# TdsReworkSMD.net
KiCad netlist of a schematic drawn in EAGLE
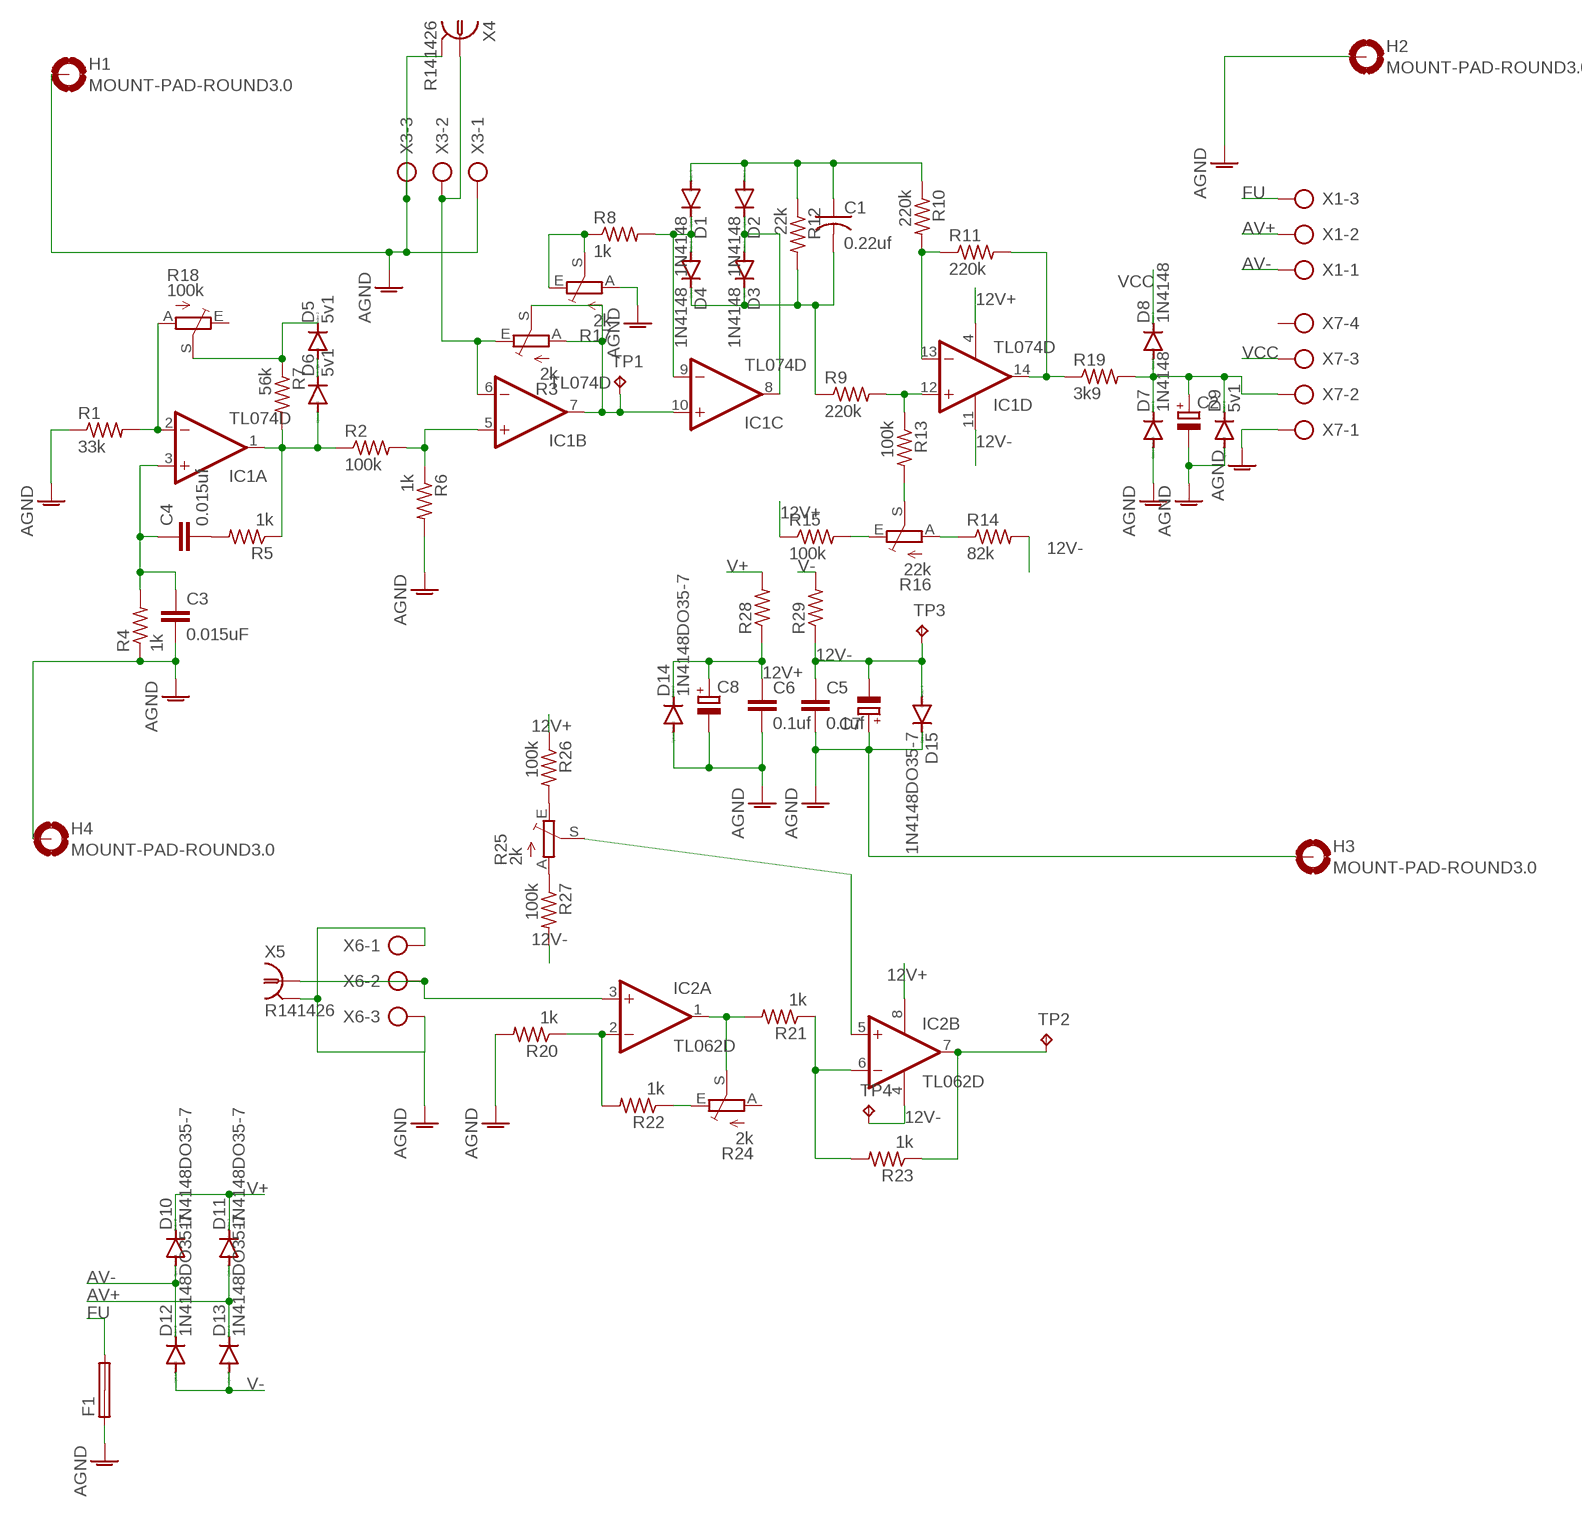
[diagram p0: schematic, sheet 1]

(export (version "E")
  (design (tool "Eeschema 10.0.6"))
  (components
    (comp (ref "C1")
      (value "0.22uf")
      (footprint "eagle-import:C075-032X103")
      (libsource (lib "eagle-import") (part "C-US075-032X103"))
    )
    (comp (ref "C2")
      (value "CPOL-EUE5-8.5")
      (footprint "eagle-import:E5-8,5")
      (libsource (lib "eagle-import") (part "CPOL-EUE5-8.5"))
    )
    (comp (ref "C3")
      (value "0.015uF")
      (footprint "eagle-import:C050-024X044")
      (libsource (lib "eagle-import") (part "C-EU050-024X044"))
    )
    (comp (ref "C4")
      (value "0.015uf")
      (footprint "eagle-import:C050-024X044")
      (libsource (lib "eagle-import") (part "C-EU050-024X044"))
    )
    (comp (ref "C5")
      (value "0.1uf")
      (footprint "eagle-import:C5B2.5")
      (libsource (lib "eagle-import") (part "C5/2.5"))
    )
    (comp (ref "C6")
      (value "0.1uf")
      (footprint "eagle-import:C5B2.5")
      (libsource (lib "eagle-import") (part "C5/2.5"))
    )
    (comp (ref "C7")
      (value "CPOL-EUE5-8.5")
      (footprint "eagle-import:E5-8,5")
      (libsource (lib "eagle-import") (part "CPOL-EUE5-8.5"))
    )
    (comp (ref "C8")
      (value "CPOL-EUE5-8.5")
      (footprint "eagle-import:E5-8,5")
      (libsource (lib "eagle-import") (part "CPOL-EUE5-8.5"))
    )
    (comp (ref "D1")
      (value "1N4148")
      (footprint "eagle-import:DO35-7")
      (libsource (lib "eagle-import") (part "1N4148DO35-7"))
    )
    (comp (ref "D2")
      (value "1N4148")
      (footprint "eagle-import:DO35-7")
      (libsource (lib "eagle-import") (part "1N4148DO35-7"))
    )
    (comp (ref "D3")
      (value "1N4148")
      (footprint "eagle-import:DO35-7")
      (libsource (lib "eagle-import") (part "1N4148DO35-7"))
    )
    (comp (ref "D4")
      (value "1N4148")
      (footprint "eagle-import:DO35-7")
      (libsource (lib "eagle-import") (part "1N4148DO35-7"))
    )
    (comp (ref "D5")
      (value "5v1")
      (footprint "eagle-import:DO35-7")
      (libsource (lib "eagle-import") (part "1N4148DO35-7"))
    )
    (comp (ref "D6")
      (value "5v1")
      (footprint "eagle-import:DO35-7")
      (libsource (lib "eagle-import") (part "1N4148DO35-7"))
    )
    (comp (ref "D7")
      (value "1N4148")
      (footprint "eagle-import:DO35-7")
      (libsource (lib "eagle-import") (part "1N4148DO35-7"))
    )
    (comp (ref "D8")
      (value "1N4148")
      (footprint "eagle-import:DO35-7")
      (libsource (lib "eagle-import") (part "1N4148DO35-7"))
    )
    (comp (ref "D9")
      (value "5v1")
      (footprint "eagle-import:DO35-10")
      (libsource (lib "eagle-import") (part "1N4148DO35-10"))
    )
    (comp (ref "D10")
      (value "1N4148DO35-7")
      (footprint "eagle-import:DO35-7")
      (libsource (lib "eagle-import") (part "1N4148DO35-7"))
    )
    (comp (ref "D11")
      (value "1N4148DO35-7")
      (footprint "eagle-import:DO35-7")
      (libsource (lib "eagle-import") (part "1N4148DO35-7"))
    )
    (comp (ref "D12")
      (value "1N4148DO35-7")
      (footprint "eagle-import:DO35-7")
      (libsource (lib "eagle-import") (part "1N4148DO35-7"))
    )
    (comp (ref "D13")
      (value "1N4148DO35-7")
      (footprint "eagle-import:DO35-7")
      (libsource (lib "eagle-import") (part "1N4148DO35-7"))
    )
    (comp (ref "D14")
      (value "1N4148DO35-7")
      (footprint "eagle-import:DO35-7")
      (libsource (lib "eagle-import") (part "1N4148DO35-7"))
    )
    (comp (ref "D15")
      (value "1N4148DO35-7")
      (footprint "eagle-import:DO35-7")
      (libsource (lib "eagle-import") (part "1N4148DO35-7"))
    )
    (comp (ref "F1")
      (value "SHK20L")
      (footprint "eagle-import:SHK20L")
      (libsource (lib "eagle-import") (part "SHK20L"))
    )
    (comp (ref "H1")
      (value "MOUNT-PAD-ROUND3.0")
      (footprint "eagle-import:3,0-PAD")
      (libsource (lib "eagle-import") (part "MOUNT-PAD-ROUND3.0"))
    )
    (comp (ref "H2")
      (value "MOUNT-PAD-ROUND3.0")
      (footprint "eagle-import:3,0-PAD")
      (libsource (lib "eagle-import") (part "MOUNT-PAD-ROUND3.0"))
    )
    (comp (ref "H3")
      (value "MOUNT-PAD-ROUND3.0")
      (footprint "eagle-import:3,0-PAD")
      (libsource (lib "eagle-import") (part "MOUNT-PAD-ROUND3.0"))
    )
    (comp (ref "H4")
      (value "MOUNT-PAD-ROUND3.0")
      (footprint "eagle-import:3,0-PAD")
      (libsource (lib "eagle-import") (part "MOUNT-PAD-ROUND3.0"))
    )
    (comp (ref "IC1")
      (value "TL074D")
      (footprint "eagle-import:SO14")
      (libsource (lib "eagle-import") (part "TL074D"))
    )
    (comp (ref "IC2")
      (value "TL062D")
      (footprint "eagle-import:SO08")
      (libsource (lib "eagle-import") (part "TL062D"))
    )
    (comp (ref "R1")
      (value "33k")
      (footprint "eagle-import:0204_5")
      (libsource (lib "eagle-import") (part "R-US_0204/5"))
    )
    (comp (ref "R2")
      (value "100k")
      (footprint "eagle-import:0204_5")
      (libsource (lib "eagle-import") (part "R-US_0204/5"))
    )
    (comp (ref "R3")
      (value "2k")
      (footprint "eagle-import:B64Y")
      (libsource (lib "eagle-import") (part "TRIM_EU-B64Y"))
    )
    (comp (ref "R4")
      (value "1k")
      (footprint "eagle-import:0204_5")
      (libsource (lib "eagle-import") (part "R-US_0204/5"))
    )
    (comp (ref "R5")
      (value "1k")
      (footprint "eagle-import:0204_5")
      (libsource (lib "eagle-import") (part "R-US_0204/5"))
    )
    (comp (ref "R6")
      (value "1k")
      (footprint "eagle-import:0204_5")
      (libsource (lib "eagle-import") (part "R-US_0204/5"))
    )
    (comp (ref "R7")
      (value "56k")
      (footprint "eagle-import:0204V")
      (libsource (lib "eagle-import") (part "R-US_0204/2V"))
    )
    (comp (ref "R8")
      (value "1k")
      (footprint "eagle-import:0204_5")
      (libsource (lib "eagle-import") (part "R-US_0204/5"))
    )
    (comp (ref "R9")
      (value "220k")
      (footprint "eagle-import:0204_5")
      (libsource (lib "eagle-import") (part "R-US_0204/5"))
    )
    (comp (ref "R10")
      (value "220k")
      (footprint "eagle-import:0204_5")
      (libsource (lib "eagle-import") (part "R-US_0204/5"))
    )
    (comp (ref "R11")
      (value "220k")
      (footprint "eagle-import:0204_5")
      (libsource (lib "eagle-import") (part "R-US_0204/5"))
    )
    (comp (ref "R12")
      (value "22k")
      (footprint "eagle-import:0204_5")
      (libsource (lib "eagle-import") (part "R-US_0204/5"))
    )
    (comp (ref "R13")
      (value "100k")
      (footprint "eagle-import:0204_5")
      (libsource (lib "eagle-import") (part "R-US_0204/5"))
    )
    (comp (ref "R14")
      (value "82k")
      (footprint "eagle-import:0204_5")
      (libsource (lib "eagle-import") (part "R-US_0204/5"))
    )
    (comp (ref "R15")
      (value "100k")
      (footprint "eagle-import:0204_5")
      (libsource (lib "eagle-import") (part "R-US_0204/5"))
    )
    (comp (ref "R16")
      (value "22k")
      (footprint "eagle-import:B64Y")
      (libsource (lib "eagle-import") (part "TRIM_EU-B64Y"))
    )
    (comp (ref "R17")
      (value "2k")
      (footprint "eagle-import:B64Y")
      (libsource (lib "eagle-import") (part "TRIM_EU-B64Y"))
    )
    (comp (ref "R18")
      (value "100k")
      (footprint "eagle-import:B64Y")
      (libsource (lib "eagle-import") (part "TRIM_EU-B64Y"))
    )
    (comp (ref "R19")
      (value "3k9")
      (footprint "eagle-import:0204_5")
      (libsource (lib "eagle-import") (part "R-US_0204/5"))
    )
    (comp (ref "R20")
      (value "1k")
      (footprint "eagle-import:0204_5")
      (libsource (lib "eagle-import") (part "R-US_0204/5"))
    )
    (comp (ref "R21")
      (value "1k")
      (footprint "eagle-import:0204_5")
      (libsource (lib "eagle-import") (part "R-US_0204/5"))
    )
    (comp (ref "R22")
      (value "1k")
      (footprint "eagle-import:0204_5")
      (libsource (lib "eagle-import") (part "R-US_0204/5"))
    )
    (comp (ref "R23")
      (value "1k")
      (footprint "eagle-import:0204_5")
      (libsource (lib "eagle-import") (part "R-US_0204/5"))
    )
    (comp (ref "R24")
      (value "2k")
      (footprint "eagle-import:B64Y")
      (libsource (lib "eagle-import") (part "TRIM_EU-B64Y"))
    )
    (comp (ref "R25")
      (value "2k")
      (footprint "eagle-import:B64Y")
      (libsource (lib "eagle-import") (part "TRIM_EU-B64Y"))
    )
    (comp (ref "R26")
      (value "100k")
      (footprint "eagle-import:0204_5")
      (libsource (lib "eagle-import") (part "R-US_0204/5"))
    )
    (comp (ref "R27")
      (value "100k")
      (footprint "eagle-import:0204_5")
      (libsource (lib "eagle-import") (part "R-US_0204/5"))
    )
    (comp (ref "R28")
      (value "R-US_0309/10")
      (footprint "eagle-import:0309_10")
      (libsource (lib "eagle-import") (part "R-US_0309/10"))
    )
    (comp (ref "R29")
      (value "R-US_0309/10")
      (footprint "eagle-import:0309_10")
      (libsource (lib "eagle-import") (part "R-US_0309/10"))
    )
    (comp (ref "TP1")
      (value "TPPAD1-13")
      (footprint "eagle-import:P1-13")
      (libsource (lib "eagle-import") (part "TPPAD1-13"))
    )
    (comp (ref "TP2")
      (value "TPPAD1-13")
      (footprint "eagle-import:P1-13")
      (libsource (lib "eagle-import") (part "TPPAD1-13"))
    )
    (comp (ref "TP3")
      (value "TPPAD1-13")
      (footprint "eagle-import:P1-13")
      (libsource (lib "eagle-import") (part "TPPAD1-13"))
    )
    (comp (ref "TP4")
      (value "TPPAD1-13")
      (footprint "eagle-import:P1-13")
      (libsource (lib "eagle-import") (part "TPPAD1-13"))
    )
    (comp (ref "X1")
      (value "AK500/3")
      (footprint "eagle-import:AK500_3")
      (libsource (lib "eagle-import") (part "AK500/3"))
    )
    (comp (ref "X3")
      (value "AK500/3")
      (footprint "eagle-import:AK500_3")
      (libsource (lib "eagle-import") (part "AK500/3"))
    )
    (comp (ref "X4")
      (value "R141426")
      (footprint "eagle-import:R141426")
      (fields (field (name "MF") "FARNELL") (field (name "MPN") "R141426161"))
      (libsource (lib "eagle-import") (part "R141426"))
    )
    (comp (ref "X5")
      (value "R141426")
      (footprint "eagle-import:R141426")
      (fields (field (name "MF") "FARNELL") (field (name "MPN") "R141426161"))
      (libsource (lib "eagle-import") (part "R141426"))
    )
    (comp (ref "X6")
      (value "AK500/3")
      (footprint "eagle-import:AK500_3")
      (libsource (lib "eagle-import") (part "AK500/3"))
    )
    (comp (ref "X7")
      (value "AK500/4")
      (footprint "eagle-import:AK500_4")
      (libsource (lib "eagle-import") (part "AK500/4"))
    )
  )
  (nets
    (net (code "1") (name "/12V+") (class "Default")
      (node (ref "C6") (pin "1") (pinfunction "1_1") (pintype "passive"))
      (node (ref "C8") (pin "+") (pinfunction "+_+") (pintype "passive"))
      (node (ref "D14") (pin "C") (pinfunction "C_C") (pintype "passive"))
      (node (ref "IC1") (pin "4") (pinfunction "V+_4") (pintype "power_in"))
      (node (ref "IC2") (pin "8") (pinfunction "V+_8") (pintype "power_in"))
      (node (ref "R15") (pin "1") (pinfunction "1_1") (pintype "passive"))
      (node (ref "R26") (pin "1") (pinfunction "1_1") (pintype "passive"))
      (node (ref "R28") (pin "1") (pinfunction "1_1") (pintype "passive"))
    )
    (net (code "2") (name "/12V-") (class "Default")
      (node (ref "C5") (pin "1") (pinfunction "1_1") (pintype "passive"))
      (node (ref "C7") (pin "-") (pinfunction "-_-") (pintype "passive"))
      (node (ref "D15") (pin "A") (pinfunction "A_A") (pintype "passive"))
      (node (ref "IC1") (pin "11") (pinfunction "V-_11") (pintype "power_in"))
      (node (ref "IC2") (pin "4") (pinfunction "V-_4") (pintype "power_in"))
      (node (ref "R14") (pin "2") (pinfunction "2_2") (pintype "passive"))
      (node (ref "R27") (pin "2") (pinfunction "2_2") (pintype "passive"))
      (node (ref "R29") (pin "1") (pinfunction "1_1") (pintype "passive"))
      (node (ref "TP3") (pin "TP") (pinfunction "TP_TP") (pintype "input"))
      (node (ref "TP4") (pin "TP") (pinfunction "TP_TP") (pintype "input"))
    )
    (net (code "3") (name "/AV+") (class "Default")
      (node (ref "D11") (pin "A") (pinfunction "A_A") (pintype "passive"))
      (node (ref "D13") (pin "C") (pinfunction "C_C") (pintype "passive"))
      (node (ref "X1") (pin "2") (pinfunction "KL_2") (pintype "passive"))
    )
    (net (code "4") (name "/AV-") (class "Default")
      (node (ref "D10") (pin "A") (pinfunction "A_A") (pintype "passive"))
      (node (ref "D12") (pin "C") (pinfunction "C_C") (pintype "passive"))
      (node (ref "X1") (pin "1") (pinfunction "KL_1") (pintype "passive"))
    )
    (net (code "5") (name "/FU") (class "Default")
      (node (ref "F1") (pin "2A") (pinfunction "2A_2A") (pintype "passive"))
      (node (ref "X1") (pin "3") (pinfunction "KL_3") (pintype "passive"))
    )
    (net (code "6") (name "/V+") (class "Default")
      (node (ref "D10") (pin "C") (pinfunction "C_C") (pintype "passive"))
      (node (ref "D11") (pin "C") (pinfunction "C_C") (pintype "passive"))
      (node (ref "R28") (pin "2") (pinfunction "2_2") (pintype "passive"))
    )
    (net (code "7") (name "/V-") (class "Default")
      (node (ref "D12") (pin "A") (pinfunction "A_A") (pintype "passive"))
      (node (ref "D13") (pin "A") (pinfunction "A_A") (pintype "passive"))
      (node (ref "R29") (pin "2") (pinfunction "2_2") (pintype "passive"))
    )
    (net (code "8") (name "/VCC") (class "Default")
      (node (ref "D8") (pin "C") (pinfunction "C_C") (pintype "passive"))
      (node (ref "X7") (pin "3") (pinfunction "KL_3") (pintype "passive"))
    )
    (net (code "9") (name "AGND") (class "Default")
      (node (ref "C2") (pin "-") (pinfunction "-_-") (pintype "passive"))
      (node (ref "C3") (pin "2") (pinfunction "2_2") (pintype "passive"))
      (node (ref "C5") (pin "2") (pinfunction "2_2") (pintype "passive"))
      (node (ref "C6") (pin "2") (pinfunction "2_2") (pintype "passive"))
      (node (ref "C7") (pin "+") (pinfunction "+_+") (pintype "passive"))
      (node (ref "C8") (pin "-") (pinfunction "-_-") (pintype "passive"))
      (node (ref "D14") (pin "A") (pinfunction "A_A") (pintype "passive"))
      (node (ref "D15") (pin "C") (pinfunction "C_C") (pintype "passive"))
      (node (ref "D7") (pin "A") (pinfunction "A_A") (pintype "passive"))
      (node (ref "D9") (pin "A") (pinfunction "A_A") (pintype "passive"))
      (node (ref "F1") (pin "1A") (pinfunction "1A_1A") (pintype "passive"))
      (node (ref "H1") (pin "B3,0") (pinfunction "MOUNT_B3,0") (pintype "passive"))
      (node (ref "H2") (pin "B3,0") (pinfunction "MOUNT_B3,0") (pintype "passive"))
      (node (ref "H3") (pin "B3,0") (pinfunction "MOUNT_B3,0") (pintype "passive"))
      (node (ref "H4") (pin "B3,0") (pinfunction "MOUNT_B3,0") (pintype "passive"))
      (node (ref "R1") (pin "1") (pinfunction "1_1") (pintype "passive"))
      (node (ref "R17") (pin "A") (pinfunction "A_A") (pintype "passive"))
      (node (ref "R20") (pin "2") (pinfunction "2_2") (pintype "passive"))
      (node (ref "R4") (pin "1") (pinfunction "1_1") (pintype "passive"))
      (node (ref "R6") (pin "2") (pinfunction "2_2") (pintype "passive"))
      (node (ref "X3") (pin "1") (pinfunction "KL_1") (pintype "passive"))
      (node (ref "X3") (pin "3") (pinfunction "KL_3") (pintype "passive"))
      (node (ref "X4") (pin "2") (pinfunction "2_2") (pintype "passive"))
      (node (ref "X4") (pin "3") (pinfunction "2_3") (pintype "passive"))
      (node (ref "X4") (pin "4") (pinfunction "2_4") (pintype "passive"))
      (node (ref "X4") (pin "5") (pinfunction "2_5") (pintype "passive"))
      (node (ref "X5") (pin "2") (pinfunction "2_2") (pintype "passive"))
      (node (ref "X5") (pin "3") (pinfunction "2_3") (pintype "passive"))
      (node (ref "X5") (pin "4") (pinfunction "2_4") (pintype "passive"))
      (node (ref "X5") (pin "5") (pinfunction "2_5") (pintype "passive"))
      (node (ref "X6") (pin "1") (pinfunction "KL_1") (pintype "passive"))
      (node (ref "X6") (pin "3") (pinfunction "KL_3") (pintype "passive"))
      (node (ref "X7") (pin "1") (pinfunction "KL_1") (pintype "passive"))
    )
    (net (code "10") (name "Net-(C1-Pad1)") (class "Default")
      (node (ref "C1") (pin "1") (pinfunction "1_1") (pintype "passive"))
      (node (ref "D1") (pin "A") (pinfunction "A_A") (pintype "passive"))
      (node (ref "D2") (pin "A") (pinfunction "A_A") (pintype "passive"))
      (node (ref "R10") (pin "1") (pinfunction "1_1") (pintype "passive"))
      (node (ref "R12") (pin "1") (pinfunction "1_1") (pintype "passive"))
    )
    (net (code "11") (name "Net-(C1-Pad2)") (class "Default")
      (node (ref "C1") (pin "2") (pinfunction "2_2") (pintype "passive"))
      (node (ref "D3") (pin "C") (pinfunction "C_C") (pintype "passive"))
      (node (ref "D4") (pin "C") (pinfunction "C_C") (pintype "passive"))
      (node (ref "R12") (pin "2") (pinfunction "2_2") (pintype "passive"))
      (node (ref "R9") (pin "1") (pinfunction "1_1") (pintype "passive"))
    )
    (net (code "12") (name "Net-(C4-Pad2)") (class "Default")
      (node (ref "C4") (pin "2") (pinfunction "2_2") (pintype "passive"))
      (node (ref "R5") (pin "2") (pinfunction "2_2") (pintype "passive"))
    )
    (net (code "13") (name "Net-(D5-PadA)") (class "Default")
      (node (ref "D5") (pin "A") (pinfunction "A_A") (pintype "passive"))
      (node (ref "D6") (pin "C") (pinfunction "C_C") (pintype "passive"))
    )
    (net (code "14") (name "Net-(D5-PadC)") (class "Default")
      (node (ref "D5") (pin "C") (pinfunction "C_C") (pintype "passive"))
      (node (ref "R18") (pin "S") (pinfunction "S_S") (pintype "passive"))
      (node (ref "R7") (pin "1") (pinfunction "1_1") (pintype "passive"))
    )
    (net (code "15") (name "Net-(IC1A-+IN)") (class "Default")
      (node (ref "C3") (pin "1") (pinfunction "1_1") (pintype "passive"))
      (node (ref "C4") (pin "1") (pinfunction "1_1") (pintype "passive"))
      (node (ref "IC1") (pin "3") (pinfunction "+IN_3") (pintype "input"))
      (node (ref "R4") (pin "2") (pinfunction "2_2") (pintype "passive"))
    )
    (net (code "16") (name "Net-(IC1A--IN)") (class "Default")
      (node (ref "IC1") (pin "2") (pinfunction "-IN_2") (pintype "input"))
      (node (ref "R1") (pin "2") (pinfunction "2_2") (pintype "passive"))
      (node (ref "R18") (pin "A") (pinfunction "A_A") (pintype "passive"))
    )
    (net (code "17") (name "Net-(IC1A-OUT)") (class "Default")
      (node (ref "D6") (pin "A") (pinfunction "A_A") (pintype "passive"))
      (node (ref "IC1") (pin "1") (pinfunction "OUT_1") (pintype "output"))
      (node (ref "R2") (pin "1") (pinfunction "1_1") (pintype "passive"))
      (node (ref "R5") (pin "1") (pinfunction "1_1") (pintype "passive"))
      (node (ref "R7") (pin "2") (pinfunction "2_2") (pintype "passive"))
    )
    (net (code "18") (name "Net-(IC1B-+IN)") (class "Default")
      (node (ref "IC1") (pin "5") (pinfunction "+IN_5") (pintype "input"))
      (node (ref "R2") (pin "2") (pinfunction "2_2") (pintype "passive"))
      (node (ref "R6") (pin "1") (pinfunction "1_1") (pintype "passive"))
    )
    (net (code "19") (name "Net-(IC1B--IN)") (class "Default")
      (node (ref "IC1") (pin "6") (pinfunction "-IN_6") (pintype "input"))
      (node (ref "R3") (pin "E") (pinfunction "E_E") (pintype "passive"))
      (node (ref "X3") (pin "2") (pinfunction "KL_2") (pintype "passive"))
      (node (ref "X4") (pin "1") (pinfunction "1_1") (pintype "passive"))
    )
    (net (code "20") (name "Net-(IC1B-OUT)") (class "Default")
      (node (ref "IC1") (pin "10") (pinfunction "+IN_10") (pintype "input"))
      (node (ref "IC1") (pin "7") (pinfunction "OUT_7") (pintype "output"))
      (node (ref "R3") (pin "A") (pinfunction "A_A") (pintype "passive"))
      (node (ref "R3") (pin "S") (pinfunction "S_S") (pintype "passive"))
      (node (ref "TP1") (pin "TP") (pinfunction "TP_TP") (pintype "input"))
    )
    (net (code "21") (name "Net-(IC1C--IN)") (class "Default")
      (node (ref "D1") (pin "C") (pinfunction "C_C") (pintype "passive"))
      (node (ref "D4") (pin "A") (pinfunction "A_A") (pintype "passive"))
      (node (ref "IC1") (pin "9") (pinfunction "-IN_9") (pintype "input"))
      (node (ref "R8") (pin "2") (pinfunction "2_2") (pintype "passive"))
    )
    (net (code "22") (name "Net-(IC1C-OUT)") (class "Default")
      (node (ref "D2") (pin "C") (pinfunction "C_C") (pintype "passive"))
      (node (ref "D3") (pin "A") (pinfunction "A_A") (pintype "passive"))
      (node (ref "IC1") (pin "8") (pinfunction "OUT_8") (pintype "output"))
    )
    (net (code "23") (name "Net-(IC1D-+IN)") (class "Default")
      (node (ref "IC1") (pin "12") (pinfunction "+IN_12") (pintype "input"))
      (node (ref "R13") (pin "1") (pinfunction "1_1") (pintype "passive"))
      (node (ref "R9") (pin "2") (pinfunction "2_2") (pintype "passive"))
    )
    (net (code "24") (name "Net-(IC1D--IN)") (class "Default")
      (node (ref "IC1") (pin "13") (pinfunction "-IN_13") (pintype "input"))
      (node (ref "R10") (pin "2") (pinfunction "2_2") (pintype "passive"))
      (node (ref "R11") (pin "1") (pinfunction "1_1") (pintype "passive"))
    )
    (net (code "25") (name "Net-(IC1D-OUT)") (class "Default")
      (node (ref "IC1") (pin "14") (pinfunction "OUT_14") (pintype "output"))
      (node (ref "R11") (pin "2") (pinfunction "2_2") (pintype "passive"))
      (node (ref "R19") (pin "1") (pinfunction "1_1") (pintype "passive"))
    )
    (net (code "26") (name "Net-(IC2A-+IN)") (class "Default")
      (node (ref "IC2") (pin "3") (pinfunction "+IN_3") (pintype "input"))
      (node (ref "X5") (pin "1") (pinfunction "1_1") (pintype "passive"))
      (node (ref "X6") (pin "2") (pinfunction "KL_2") (pintype "passive"))
    )
    (net (code "27") (name "Net-(IC2A--IN)") (class "Default")
      (node (ref "IC2") (pin "2") (pinfunction "-IN_2") (pintype "input"))
      (node (ref "R20") (pin "1") (pinfunction "1_1") (pintype "passive"))
      (node (ref "R22") (pin "2") (pinfunction "2_2") (pintype "passive"))
    )
    (net (code "28") (name "Net-(IC2A-OUT)") (class "Default")
      (node (ref "IC2") (pin "1") (pinfunction "OUT_1") (pintype "output"))
      (node (ref "R21") (pin "2") (pinfunction "2_2") (pintype "passive"))
      (node (ref "R24") (pin "S") (pinfunction "S_S") (pintype "passive"))
    )
    (net (code "29") (name "Net-(IC2B-+IN)") (class "Default")
      (node (ref "IC2") (pin "5") (pinfunction "+IN_5") (pintype "input"))
      (node (ref "R25") (pin "S") (pinfunction "S_S") (pintype "passive"))
    )
    (net (code "30") (name "Net-(IC2B--IN)") (class "Default")
      (node (ref "IC2") (pin "6") (pinfunction "-IN_6") (pintype "input"))
      (node (ref "R21") (pin "1") (pinfunction "1_1") (pintype "passive"))
      (node (ref "R23") (pin "2") (pinfunction "2_2") (pintype "passive"))
    )
    (net (code "31") (name "Net-(IC2B-OUT)") (class "Default")
      (node (ref "IC2") (pin "7") (pinfunction "OUT_7") (pintype "output"))
      (node (ref "R23") (pin "1") (pinfunction "1_1") (pintype "passive"))
      (node (ref "TP2") (pin "TP") (pinfunction "TP_TP") (pintype "input"))
    )
    (net (code "32") (name "Net-(R13-Pad2)") (class "Default")
      (node (ref "R13") (pin "2") (pinfunction "2_2") (pintype "passive"))
      (node (ref "R16") (pin "S") (pinfunction "S_S") (pintype "passive"))
    )
    (net (code "33") (name "Net-(R14-Pad1)") (class "Default")
      (node (ref "R14") (pin "1") (pinfunction "1_1") (pintype "passive"))
      (node (ref "R16") (pin "A") (pinfunction "A_A") (pintype "passive"))
    )
    (net (code "34") (name "Net-(R15-Pad2)") (class "Default")
      (node (ref "R15") (pin "2") (pinfunction "2_2") (pintype "passive"))
      (node (ref "R16") (pin "E") (pinfunction "E_E") (pintype "passive"))
    )
    (net (code "35") (name "Net-(R17-PadE)") (class "Default")
      (node (ref "R17") (pin "E") (pinfunction "E_E") (pintype "passive"))
      (node (ref "R17") (pin "S") (pinfunction "S_S") (pintype "passive"))
      (node (ref "R8") (pin "1") (pinfunction "1_1") (pintype "passive"))
    )
    (net (code "36") (name "Net-(R22-Pad1)") (class "Default")
      (node (ref "R22") (pin "1") (pinfunction "1_1") (pintype "passive"))
      (node (ref "R24") (pin "E") (pinfunction "E_E") (pintype "passive"))
    )
    (net (code "37") (name "Net-(R25-PadA)") (class "Default")
      (node (ref "R25") (pin "A") (pinfunction "A_A") (pintype "passive"))
      (node (ref "R27") (pin "1") (pinfunction "1_1") (pintype "passive"))
    )
    (net (code "38") (name "Net-(R25-PadE)") (class "Default")
      (node (ref "R25") (pin "E") (pinfunction "E_E") (pintype "passive"))
      (node (ref "R26") (pin "2") (pinfunction "2_2") (pintype "passive"))
    )
    (net (code "39") (name "Net-(X7B-KL)") (class "Default")
      (node (ref "C2") (pin "+") (pinfunction "+_+") (pintype "passive"))
      (node (ref "D7") (pin "C") (pinfunction "C_C") (pintype "passive"))
      (node (ref "D8") (pin "A") (pinfunction "A_A") (pintype "passive"))
      (node (ref "D9") (pin "C") (pinfunction "C_C") (pintype "passive"))
      (node (ref "R19") (pin "2") (pinfunction "2_2") (pintype "passive"))
      (node (ref "X7") (pin "2") (pinfunction "KL_2") (pintype "passive"))
    )
    (net (code "40") (name "unconnected-(F1-Pad1B)") (class "Default")
      (node (ref "F1") (pin "1B") (pinfunction "1B_1B") (pintype "passive"))
    )
    (net (code "41") (name "unconnected-(F1-Pad2B)") (class "Default")
      (node (ref "F1") (pin "2B") (pinfunction "2B_2B") (pintype "passive"))
    )
    (net (code "42") (name "unconnected-(R18-PadE)") (class "Default")
      (node (ref "R18") (pin "E") (pinfunction "E_E") (pintype "passive"))
    )
    (net (code "43") (name "unconnected-(R24-PadA)") (class "Default")
      (node (ref "R24") (pin "A") (pinfunction "A_A") (pintype "passive"))
    )
    (net (code "44") (name "unconnected-(X7D-KL-Pad4)") (class "Default")
      (node (ref "X7") (pin "4") (pinfunction "KL_4") (pintype "passive"))
    )
  )
)
